# Sh_ADC-DAC_Main.net
KiCad netlist of a schematic drawn in Altium Designer
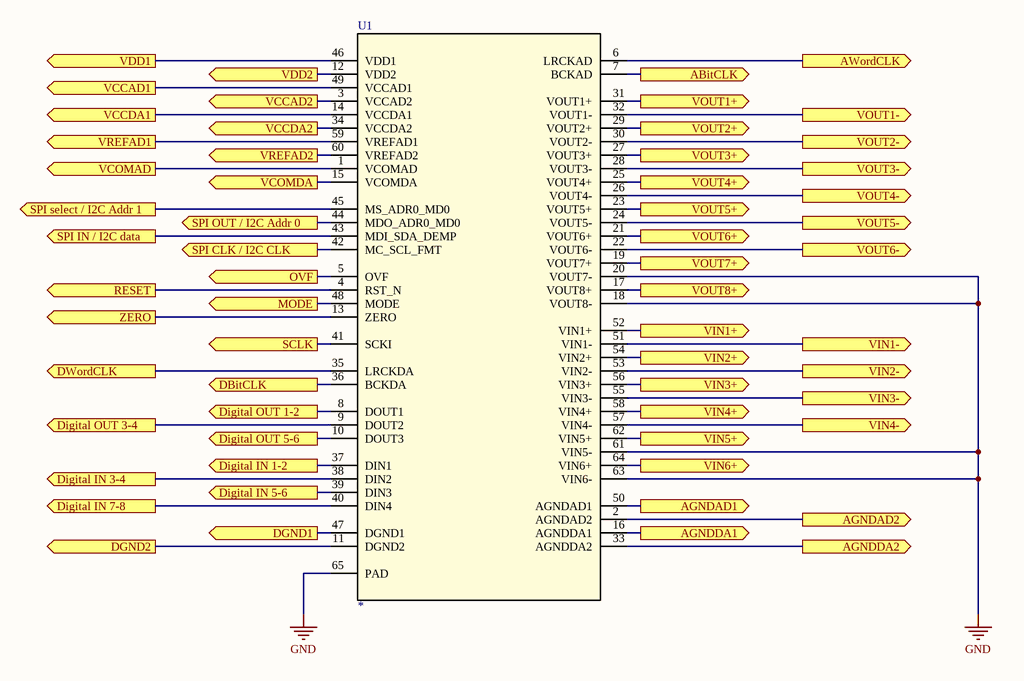
[diagram p0: Sh_ADC-DAC_Main.SchDoc]

(export (version "E")
  (design (tool "Eeschema 10.0.6"))
  (components
    (comp (ref "U1")
      (value "*")
      (footprint "PAP0064J_N")
      (description "Imported")
      (fields (field (name "PARTNUMBER") "PCM3168APAPR") (field (name "MANUFACTURER") "Texas Instruments"))
      (libsource (lib "Bonjour") (part "PCM3168APAPR"))
    )
  )
  (nets
    (net (code "1") (name "/ABitCLK") (class "Default")
      (node (ref "U1") (pin "7") (pinfunction "BCKAD_7") (pintype "passive"))
    )
    (net (code "2") (name "/AGNDAD1") (class "Default")
      (node (ref "U1") (pin "50") (pinfunction "AGNDAD1_50") (pintype "passive"))
    )
    (net (code "3") (name "/AGNDAD2") (class "Default")
      (node (ref "U1") (pin "2") (pinfunction "AGNDAD2_2") (pintype "passive"))
    )
    (net (code "4") (name "/AGNDDA1") (class "Default")
      (node (ref "U1") (pin "16") (pinfunction "AGNDDA1_16") (pintype "passive"))
    )
    (net (code "5") (name "/AGNDDA2") (class "Default")
      (node (ref "U1") (pin "33") (pinfunction "AGNDDA2_33") (pintype "passive"))
    )
    (net (code "6") (name "/AWordCLK") (class "Default")
      (node (ref "U1") (pin "6") (pinfunction "LRCKAD_6") (pintype "passive"))
    )
    (net (code "7") (name "/DBitCLK") (class "Default")
      (node (ref "U1") (pin "36") (pinfunction "BCKDA_36") (pintype "passive"))
    )
    (net (code "8") (name "/DGND1") (class "Default")
      (node (ref "U1") (pin "47") (pinfunction "DGND1_47") (pintype "passive"))
    )
    (net (code "9") (name "/DGND2") (class "Default")
      (node (ref "U1") (pin "11") (pinfunction "DGND2_11") (pintype "passive"))
    )
    (net (code "10") (name "/DWordCLK") (class "Default")
      (node (ref "U1") (pin "35") (pinfunction "LRCKDA_35") (pintype "passive"))
    )
    (net (code "11") (name "/Digital IN 1-2") (class "Default")
      (node (ref "U1") (pin "37") (pinfunction "DIN1_37") (pintype "passive"))
    )
    (net (code "12") (name "/Digital IN 3-4") (class "Default")
      (node (ref "U1") (pin "38") (pinfunction "DIN2_38") (pintype "passive"))
    )
    (net (code "13") (name "/Digital IN 5-6") (class "Default")
      (node (ref "U1") (pin "39") (pinfunction "DIN3_39") (pintype "passive"))
    )
    (net (code "14") (name "/Digital IN 7-8") (class "Default")
      (node (ref "U1") (pin "40") (pinfunction "DIN4_40") (pintype "passive"))
    )
    (net (code "15") (name "/Digital OUT 1-2") (class "Default")
      (node (ref "U1") (pin "8") (pinfunction "DOUT1_8") (pintype "passive"))
    )
    (net (code "16") (name "/Digital OUT 3-4") (class "Default")
      (node (ref "U1") (pin "9") (pinfunction "DOUT2_9") (pintype "passive"))
    )
    (net (code "17") (name "/Digital OUT 5-6") (class "Default")
      (node (ref "U1") (pin "10") (pinfunction "DOUT3_10") (pintype "passive"))
    )
    (net (code "18") (name "/MODE") (class "Default")
      (node (ref "U1") (pin "48") (pinfunction "MODE_48") (pintype "passive"))
    )
    (net (code "19") (name "/OVF") (class "Default")
      (node (ref "U1") (pin "5") (pinfunction "OVF_5") (pintype "passive"))
    )
    (net (code "20") (name "/RESET") (class "Default")
      (node (ref "U1") (pin "4") (pinfunction "RST_N_4") (pintype "passive"))
    )
    (net (code "21") (name "/SCLK") (class "Default")
      (node (ref "U1") (pin "41") (pinfunction "SCKI_41") (pintype "passive"))
    )
    (net (code "22") (name "/SPI CLK {slash} I2C CLK") (class "Default")
      (node (ref "U1") (pin "42") (pinfunction "MC_SCL_FMT_42") (pintype "passive"))
    )
    (net (code "23") (name "/SPI IN {slash} I2C data") (class "Default")
      (node (ref "U1") (pin "43") (pinfunction "MDI_SDA_DEMP_43") (pintype "passive"))
    )
    (net (code "24") (name "/SPI OUT {slash} I2C Addr 0") (class "Default")
      (node (ref "U1") (pin "44") (pinfunction "MDO_ADR0_MD0_44") (pintype "passive"))
    )
    (net (code "25") (name "/SPI select {slash} I2C Addr 1") (class "Default")
      (node (ref "U1") (pin "45") (pinfunction "MS_ADR0_MD0_45") (pintype "passive"))
    )
    (net (code "26") (name "/VCCAD1") (class "Default")
      (node (ref "U1") (pin "49") (pinfunction "VCCAD1_49") (pintype "passive"))
    )
    (net (code "27") (name "/VCCAD2") (class "Default")
      (node (ref "U1") (pin "3") (pinfunction "VCCAD2_3") (pintype "passive"))
    )
    (net (code "28") (name "/VCCDA1") (class "Default")
      (node (ref "U1") (pin "14") (pinfunction "VCCDA1_14") (pintype "passive"))
    )
    (net (code "29") (name "/VCCDA2") (class "Default")
      (node (ref "U1") (pin "34") (pinfunction "VCCDA2_34") (pintype "passive"))
    )
    (net (code "30") (name "/VCOMAD") (class "Default")
      (node (ref "U1") (pin "1") (pinfunction "VCOMAD_1") (pintype "passive"))
    )
    (net (code "31") (name "/VCOMDA") (class "Default")
      (node (ref "U1") (pin "15") (pinfunction "VCOMDA_15") (pintype "passive"))
    )
    (net (code "32") (name "/VDD1") (class "Default")
      (node (ref "U1") (pin "46") (pinfunction "VDD1_46") (pintype "passive"))
    )
    (net (code "33") (name "/VDD2") (class "Default")
      (node (ref "U1") (pin "12") (pinfunction "VDD2_12") (pintype "passive"))
    )
    (net (code "34") (name "/VIN1+") (class "Default")
      (node (ref "U1") (pin "52") (pinfunction "VIN1+_52") (pintype "passive"))
    )
    (net (code "35") (name "/VIN1-") (class "Default")
      (node (ref "U1") (pin "51") (pinfunction "VIN1-_51") (pintype "passive"))
    )
    (net (code "36") (name "/VIN2+") (class "Default")
      (node (ref "U1") (pin "54") (pinfunction "VIN2+_54") (pintype "passive"))
    )
    (net (code "37") (name "/VIN2-") (class "Default")
      (node (ref "U1") (pin "53") (pinfunction "VIN2-_53") (pintype "passive"))
    )
    (net (code "38") (name "/VIN3+") (class "Default")
      (node (ref "U1") (pin "56") (pinfunction "VIN3+_56") (pintype "passive"))
    )
    (net (code "39") (name "/VIN3-") (class "Default")
      (node (ref "U1") (pin "55") (pinfunction "VIN3-_55") (pintype "passive"))
    )
    (net (code "40") (name "/VIN4+") (class "Default")
      (node (ref "U1") (pin "58") (pinfunction "VIN4+_58") (pintype "passive"))
    )
    (net (code "41") (name "/VIN4-") (class "Default")
      (node (ref "U1") (pin "57") (pinfunction "VIN4-_57") (pintype "passive"))
    )
    (net (code "42") (name "/VIN5+") (class "Default")
      (node (ref "U1") (pin "62") (pinfunction "VIN5+_62") (pintype "passive"))
    )
    (net (code "43") (name "/VIN6+") (class "Default")
      (node (ref "U1") (pin "64") (pinfunction "VIN6+_64") (pintype "passive"))
    )
    (net (code "44") (name "/VOUT1+") (class "Default")
      (node (ref "U1") (pin "31") (pinfunction "VOUT1+_31") (pintype "passive"))
    )
    (net (code "45") (name "/VOUT1-") (class "Default")
      (node (ref "U1") (pin "32") (pinfunction "VOUT1-_32") (pintype "passive"))
    )
    (net (code "46") (name "/VOUT2+") (class "Default")
      (node (ref "U1") (pin "29") (pinfunction "VOUT2+_29") (pintype "passive"))
    )
    (net (code "47") (name "/VOUT2-") (class "Default")
      (node (ref "U1") (pin "30") (pinfunction "VOUT2-_30") (pintype "passive"))
    )
    (net (code "48") (name "/VOUT3+") (class "Default")
      (node (ref "U1") (pin "27") (pinfunction "VOUT3+_27") (pintype "passive"))
    )
    (net (code "49") (name "/VOUT3-") (class "Default")
      (node (ref "U1") (pin "28") (pinfunction "VOUT3-_28") (pintype "passive"))
    )
    (net (code "50") (name "/VOUT4+") (class "Default")
      (node (ref "U1") (pin "25") (pinfunction "VOUT4+_25") (pintype "passive"))
    )
    (net (code "51") (name "/VOUT4-") (class "Default")
      (node (ref "U1") (pin "26") (pinfunction "VOUT4-_26") (pintype "passive"))
    )
    (net (code "52") (name "/VOUT5+") (class "Default")
      (node (ref "U1") (pin "23") (pinfunction "VOUT5+_23") (pintype "passive"))
    )
    (net (code "53") (name "/VOUT5-") (class "Default")
      (node (ref "U1") (pin "24") (pinfunction "VOUT5-_24") (pintype "passive"))
    )
    (net (code "54") (name "/VOUT6+") (class "Default")
      (node (ref "U1") (pin "21") (pinfunction "VOUT6+_21") (pintype "passive"))
    )
    (net (code "55") (name "/VOUT6-") (class "Default")
      (node (ref "U1") (pin "22") (pinfunction "VOUT6-_22") (pintype "passive"))
    )
    (net (code "56") (name "/VOUT7+") (class "Default")
      (node (ref "U1") (pin "19") (pinfunction "VOUT7+_19") (pintype "passive"))
    )
    (net (code "57") (name "/VOUT8+") (class "Default")
      (node (ref "U1") (pin "17") (pinfunction "VOUT8+_17") (pintype "passive"))
    )
    (net (code "58") (name "/VREFAD1") (class "Default")
      (node (ref "U1") (pin "59") (pinfunction "VREFAD1_59") (pintype "passive"))
    )
    (net (code "59") (name "/VREFAD2") (class "Default")
      (node (ref "U1") (pin "60") (pinfunction "VREFAD2_60") (pintype "passive"))
    )
    (net (code "60") (name "/ZERO") (class "Default")
      (node (ref "U1") (pin "13") (pinfunction "ZERO_13") (pintype "passive"))
    )
    (net (code "61") (name "GND") (class "Default")
      (node (ref "U1") (pin "18") (pinfunction "VOUT8-_18") (pintype "passive"))
      (node (ref "U1") (pin "20") (pinfunction "VOUT7-_20") (pintype "passive"))
      (node (ref "U1") (pin "61") (pinfunction "VIN5-_61") (pintype "passive"))
      (node (ref "U1") (pin "63") (pinfunction "VIN6-_63") (pintype "passive"))
      (node (ref "U1") (pin "65") (pinfunction "PAD_65") (pintype "passive"))
    )
  )
)
